# proj_controle.net
KiCad netlist of a schematic drawn in EAGLE
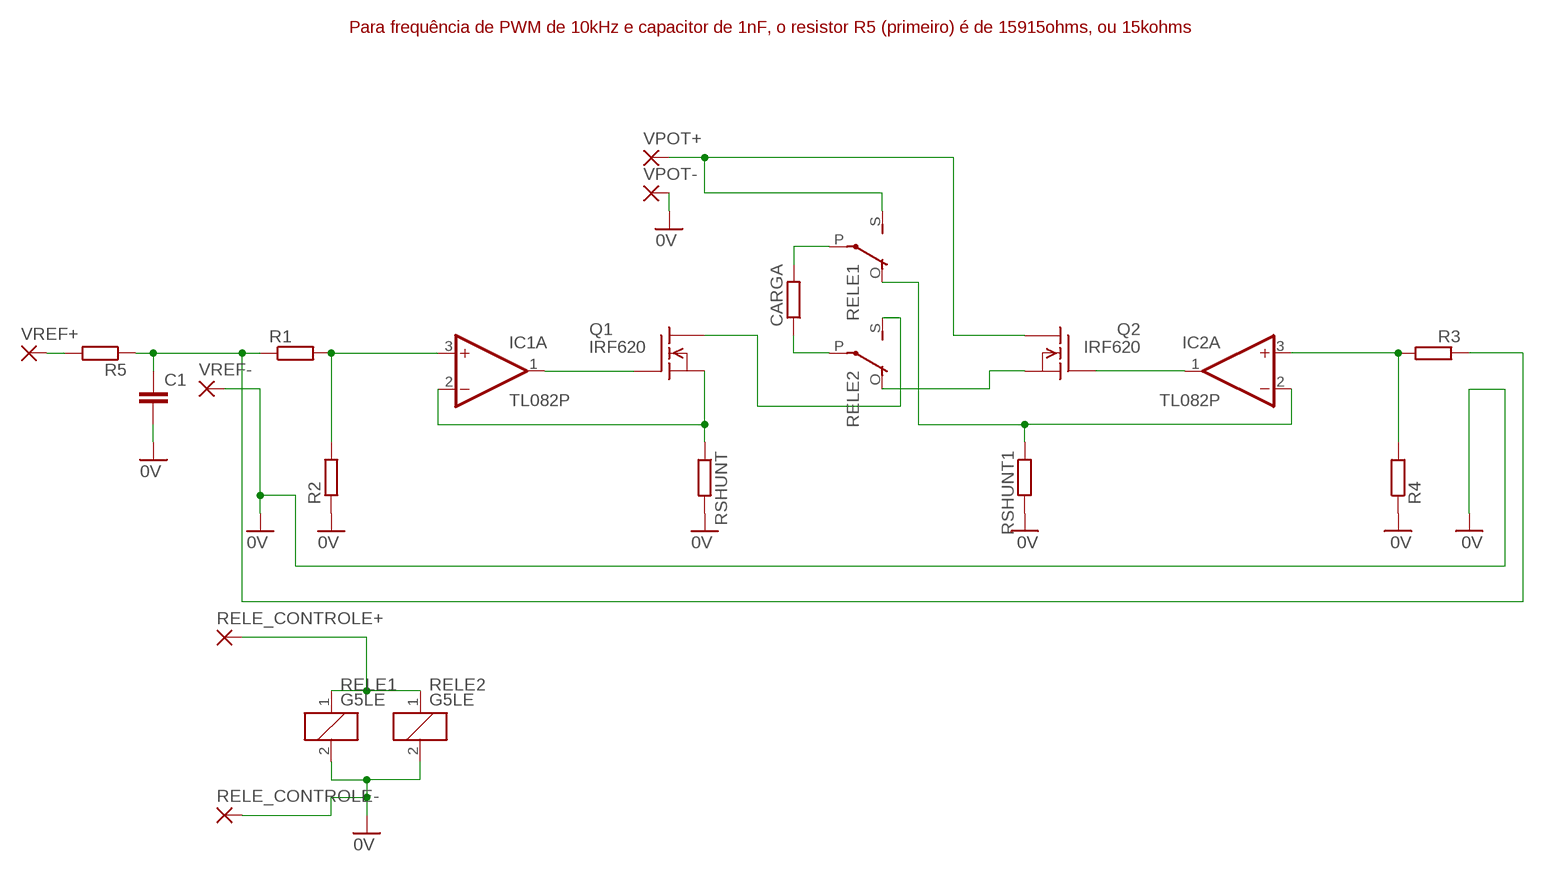
[diagram p0: schematic, sheet 1]

(export (version "E")
  (design (tool "Eeschema 10.0.6"))
  (components
    (comp (ref "C1")
      (value "C-EU050-025X075")
      (footprint "eagle-import:C050-025X075")
      (libsource (lib "eagle-import") (part "C-EU050-025X075"))
    )
    (comp (ref "CARGA")
      (value "R-EU_0207/10")
      (footprint "eagle-import:0207_10")
      (libsource (lib "eagle-import") (part "R-EU_0207/10"))
    )
    (comp (ref "IC1")
      (value "TL082P")
      (footprint "eagle-import:DIL08")
      (libsource (lib "eagle-import") (part "TL082P"))
    )
    (comp (ref "IC2")
      (value "TL082P")
      (footprint "eagle-import:DIL08")
      (libsource (lib "eagle-import") (part "TL082P"))
    )
    (comp (ref "Q1")
      (value "IRF620")
      (footprint "eagle-import:TO220")
      (libsource (lib "eagle-import") (part "IRF620"))
    )
    (comp (ref "Q2")
      (value "IRF620")
      (footprint "eagle-import:TO220")
      (libsource (lib "eagle-import") (part "IRF620"))
    )
    (comp (ref "R1")
      (value "R-EU_0207/10")
      (footprint "eagle-import:0207_10")
      (libsource (lib "eagle-import") (part "R-EU_0207/10"))
    )
    (comp (ref "R2")
      (value "R-EU_0207/10")
      (footprint "eagle-import:0207_10")
      (libsource (lib "eagle-import") (part "R-EU_0207/10"))
    )
    (comp (ref "R3")
      (value "R-EU_0207/10")
      (footprint "eagle-import:0207_10")
      (libsource (lib "eagle-import") (part "R-EU_0207/10"))
    )
    (comp (ref "R4")
      (value "R-EU_0207/10")
      (footprint "eagle-import:0207_10")
      (libsource (lib "eagle-import") (part "R-EU_0207/10"))
    )
    (comp (ref "R5")
      (value "R-EU_0207/10")
      (footprint "eagle-import:0207_10")
      (libsource (lib "eagle-import") (part "R-EU_0207/10"))
    )
    (comp (ref "RELE1")
      (value "G5LE")
      (footprint "eagle-import:G5LE")
      (libsource (lib "eagle-import") (part "G5LE"))
    )
    (comp (ref "RELE2")
      (value "G5LE")
      (footprint "eagle-import:G5LE")
      (libsource (lib "eagle-import") (part "G5LE"))
    )
    (comp (ref "RELE_CONTROLE+")
      (value "3,17/1,1")
      (footprint "eagle-import:3,17_1,1")
      (libsource (lib "eagle-import") (part "3,17/1,1"))
    )
    (comp (ref "RELE_CONTROLE-")
      (value "3,17/1,1")
      (footprint "eagle-import:3,17_1,1")
      (libsource (lib "eagle-import") (part "3,17/1,1"))
    )
    (comp (ref "RSHUNT")
      (value "R-EU_0617/22")
      (footprint "eagle-import:0617_22")
      (libsource (lib "eagle-import") (part "resistor_R-EU_0617/22"))
    )
    (comp (ref "RSHUNT1")
      (value "R-EU_0617/22")
      (footprint "eagle-import:0617_22")
      (libsource (lib "eagle-import") (part "resistor_R-EU_0617/22"))
    )
    (comp (ref "VPOT+")
      (value "3,17/1,1")
      (footprint "eagle-import:3,17_1,1")
      (libsource (lib "eagle-import") (part "3,17/1,1"))
    )
    (comp (ref "VPOT-")
      (value "3,17/1,1")
      (footprint "eagle-import:3,17_1,1")
      (libsource (lib "eagle-import") (part "3,17/1,1"))
    )
    (comp (ref "VREF+")
      (value "3,17/1,1")
      (footprint "eagle-import:3,17_1,1")
      (libsource (lib "eagle-import") (part "3,17/1,1"))
    )
    (comp (ref "VREF-")
      (value "3,17/1,1")
      (footprint "eagle-import:3,17_1,1")
      (libsource (lib "eagle-import") (part "3,17/1,1"))
    )
  )
  (nets
    (net (code "1") (name "0V") (class "Default")
      (node (ref "C1") (pin "2") (pinfunction "2_2") (pintype "passive"))
      (node (ref "R2") (pin "1") (pinfunction "1_1") (pintype "passive"))
      (node (ref "R4") (pin "1") (pinfunction "1_1") (pintype "passive"))
      (node (ref "RELE1") (pin "2") (pinfunction "2_2") (pintype "passive"))
      (node (ref "RELE2") (pin "2") (pinfunction "2_2") (pintype "passive"))
      (node (ref "RELE_CONTROLE-") (pin "1") (pinfunction "P_1") (pintype "passive"))
      (node (ref "RSHUNT") (pin "2") (pinfunction "2_2") (pintype "passive"))
      (node (ref "RSHUNT1") (pin "2") (pinfunction "2_2") (pintype "passive"))
      (node (ref "VPOT-") (pin "1") (pinfunction "P_1") (pintype "passive"))
      (node (ref "VREF-") (pin "1") (pinfunction "P_1") (pintype "passive"))
    )
    (net (code "2") (name "Net-(C1-Pad1)") (class "Default")
      (node (ref "C1") (pin "1") (pinfunction "1_1") (pintype "passive"))
      (node (ref "R1") (pin "1") (pinfunction "1_1") (pintype "passive"))
      (node (ref "R3") (pin "1") (pinfunction "1_1") (pintype "passive"))
      (node (ref "R5") (pin "1") (pinfunction "1_1") (pintype "passive"))
    )
    (net (code "3") (name "Net-(CARGA-Pad1)") (class "Default")
      (node (ref "CARGA") (pin "1") (pinfunction "1_1") (pintype "passive"))
      (node (ref "RELE2") (pin "P") (pinfunction "P_P") (pintype "passive"))
    )
    (net (code "4") (name "Net-(CARGA-Pad2)") (class "Default")
      (node (ref "CARGA") (pin "2") (pinfunction "2_2") (pintype "passive"))
      (node (ref "RELE1") (pin "P") (pinfunction "P_P") (pintype "passive"))
    )
    (net (code "5") (name "Net-(IC1A-+IN)") (class "Default")
      (node (ref "IC1") (pin "3") (pinfunction "+IN_3") (pintype "input"))
      (node (ref "R1") (pin "2") (pinfunction "2_2") (pintype "passive"))
      (node (ref "R2") (pin "2") (pinfunction "2_2") (pintype "passive"))
    )
    (net (code "6") (name "Net-(IC1A--IN)") (class "Default")
      (node (ref "IC1") (pin "2") (pinfunction "-IN_2") (pintype "input"))
      (node (ref "Q1") (pin "3") (pinfunction "S_3") (pintype "passive"))
      (node (ref "RSHUNT") (pin "1") (pinfunction "1_1") (pintype "passive"))
    )
    (net (code "7") (name "Net-(IC1A-OUT)") (class "Default")
      (node (ref "IC1") (pin "1") (pinfunction "OUT_1") (pintype "output"))
      (node (ref "Q1") (pin "1") (pinfunction "G_1") (pintype "passive"))
    )
    (net (code "8") (name "Net-(IC2A-+IN)") (class "Default")
      (node (ref "IC2") (pin "3") (pinfunction "+IN_3") (pintype "input"))
      (node (ref "R3") (pin "2") (pinfunction "2_2") (pintype "passive"))
      (node (ref "R4") (pin "2") (pinfunction "2_2") (pintype "passive"))
    )
    (net (code "9") (name "Net-(IC2A--IN)") (class "Default")
      (node (ref "IC2") (pin "2") (pinfunction "-IN_2") (pintype "input"))
      (node (ref "RELE1") (pin "O") (pinfunction "O_O") (pintype "passive"))
      (node (ref "RSHUNT1") (pin "1") (pinfunction "1_1") (pintype "passive"))
    )
    (net (code "10") (name "Net-(IC2A-OUT)") (class "Default")
      (node (ref "IC2") (pin "1") (pinfunction "OUT_1") (pintype "output"))
      (node (ref "Q2") (pin "1") (pinfunction "G_1") (pintype "passive"))
    )
    (net (code "11") (name "Net-(Q1-D)") (class "Default")
      (node (ref "Q1") (pin "2") (pinfunction "D_2") (pintype "passive"))
      (node (ref "RELE2") (pin "S") (pinfunction "S_S") (pintype "passive"))
    )
    (net (code "12") (name "Net-(Q2-D)") (class "Default")
      (node (ref "Q2") (pin "2") (pinfunction "D_2") (pintype "passive"))
      (node (ref "RELE1") (pin "S") (pinfunction "S_S") (pintype "passive"))
      (node (ref "VPOT+") (pin "1") (pinfunction "P_1") (pintype "passive"))
    )
    (net (code "13") (name "Net-(Q2-S)") (class "Default")
      (node (ref "Q2") (pin "3") (pinfunction "S_3") (pintype "passive"))
      (node (ref "RELE2") (pin "O") (pinfunction "O_O") (pintype "passive"))
    )
    (net (code "14") (name "Net-(RELE_CONTROLE+-P)") (class "Default")
      (node (ref "RELE1") (pin "1") (pinfunction "1_1") (pintype "passive"))
      (node (ref "RELE2") (pin "1") (pinfunction "1_1") (pintype "passive"))
      (node (ref "RELE_CONTROLE+") (pin "1") (pinfunction "P_1") (pintype "passive"))
    )
    (net (code "15") (name "Net-(VREF+-P)") (class "Default")
      (node (ref "R5") (pin "2") (pinfunction "2_2") (pintype "passive"))
      (node (ref "VREF+") (pin "1") (pinfunction "P_1") (pintype "passive"))
    )
  )
)
